# MMA8452QT_I2C.net
KiCad netlist of a schematic drawn in Altium Designer
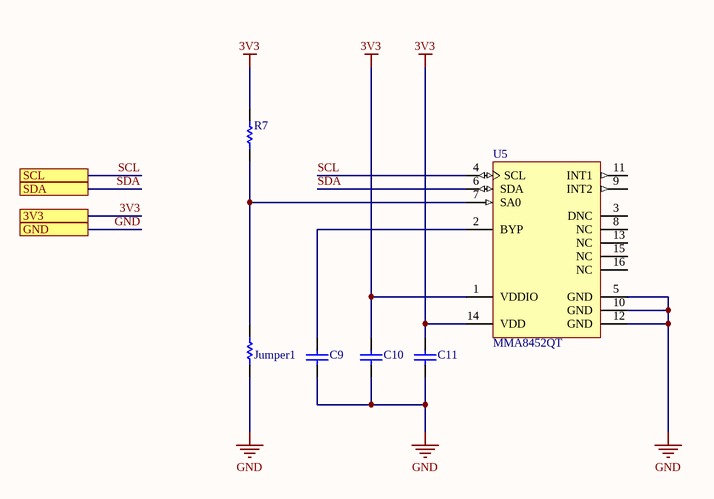
[diagram p0: MMA8452QT_I2C.SchDoc]

(export (version "E")
  (design (tool "Eeschema 10.0.6"))
  (components
    (comp (ref "C9")
      (value "C0805C104J5RAC7800")
      (footprint "CAPC2013X145X50NL20T25")
      (description "0.1µF ±5% 50V Ceramic Capacitor X7R 0805 (2012 Metric)")
      (fields (field (name "MANUFACTURER") "Kemet"))
      (libsource (lib "Altium Content Vault") (part "CAP"))
    )
    (comp (ref "C10")
      (value "C0805C104J5RAC7800")
      (footprint "CAPC2013X145X50NL20T25")
      (description "0.1µF ±5% 50V Ceramic Capacitor X7R 0805 (2012 Metric)")
      (fields (field (name "MANUFACTURER") "Kemet"))
      (libsource (lib "Altium Content Vault") (part "CAP"))
    )
    (comp (ref "C11")
      (value "08053D475KAT2A")
      (footprint "CAPC2013X140X50NL20T25")
      (description "4.7µF ±10% 25V Ceramic Capacitor X5R 0805 (2012 Metric)")
      (fields (field (name "MANUFACTURER") "AVX Interconnect / Elco"))
      (libsource (lib "Altium Content Vault") (part "CAP"))
    )
    (comp (ref "Jumper1")
      (value "~")
      (footprint "RESC2013X60X40NL20T25_A")
      (fields (field (name "TOLERANCE") "0.1%") (field (name "MANUFACTURER") "Panasonic"))
      (libsource (lib "Altium Content Vault") (part "RES-2"))
    )
    (comp (ref "R7")
      (value "RK73B2ATTD103J")
      (footprint "RESC2013X60X30NL20T20")
      (fields (field (name "MANUFACTURER") "KOA Speer"))
      (libsource (lib "Altium Content Vault") (part "RES"))
    )
    (comp (ref "U5")
      (value "MMA8452QT")
      (footprint "FRES-SOT1676-1_V")
      (fields (field (name "MANUFACTURER") "Freescale"))
      (libsource (lib "Altium Content Vault") (part "FRES-MMA8452Q-QFN-16"))
    )
  )
  (nets
    (net (code "1") (name "/SCL") (class "Default")
      (node (ref "U5") (pin "4") (pinfunction "SCL_4") (pintype "bidirectional"))
    )
    (net (code "2") (name "/SDA") (class "Default")
      (node (ref "U5") (pin "6") (pinfunction "SDA_6") (pintype "bidirectional"))
    )
    (net (code "3") (name "3V3") (class "Default")
      (node (ref "C10") (pin "2") (pinfunction "2_2") (pintype "passive"))
      (node (ref "C11") (pin "2") (pinfunction "2_2") (pintype "passive"))
      (node (ref "R7") (pin "2") (pinfunction "2_2") (pintype "passive"))
      (node (ref "U5") (pin "1") (pinfunction "VDDIO_1") (pintype "power_in"))
      (node (ref "U5") (pin "14") (pinfunction "VDD_14") (pintype "power_in"))
    )
    (net (code "4") (name "GND") (class "Default")
      (node (ref "C10") (pin "1") (pinfunction "1_1") (pintype "passive"))
      (node (ref "C11") (pin "1") (pinfunction "1_1") (pintype "passive"))
      (node (ref "C9") (pin "1") (pinfunction "1_1") (pintype "passive"))
      (node (ref "Jumper1") (pin "1") (pinfunction "1_1") (pintype "passive"))
      (node (ref "U5") (pin "10") (pinfunction "GND_10") (pintype "power_in"))
      (node (ref "U5") (pin "12") (pinfunction "GND_12") (pintype "power_in"))
      (node (ref "U5") (pin "5") (pinfunction "GND_5") (pintype "power_in"))
    )
    (net (code "5") (name "Net-(U5-BYP)") (class "Default")
      (node (ref "C9") (pin "2") (pinfunction "2_2") (pintype "passive"))
      (node (ref "U5") (pin "2") (pinfunction "BYP_2") (pintype "passive"))
    )
    (net (code "6") (name "Net-(U5-SA0)") (class "Default")
      (node (ref "Jumper1") (pin "2") (pinfunction "2_2") (pintype "passive"))
      (node (ref "R7") (pin "1") (pinfunction "1_1") (pintype "passive"))
      (node (ref "U5") (pin "7") (pinfunction "SA0_7") (pintype "input"))
    )
    (net (code "7") (name "unconnected-(U5-DNC-Pad3)") (class "Default")
      (node (ref "U5") (pin "3") (pinfunction "DNC_3") (pintype "passive"))
    )
    (net (code "8") (name "unconnected-(U5-INT1-Pad11)") (class "Default")
      (node (ref "U5") (pin "11") (pinfunction "INT1_11") (pintype "output"))
    )
    (net (code "9") (name "unconnected-(U5-INT2-Pad9)") (class "Default")
      (node (ref "U5") (pin "9") (pinfunction "INT2_9") (pintype "output"))
    )
    (net (code "10") (name "unconnected-(U5-NC-Pad8)") (class "Default")
      (node (ref "U5") (pin "8") (pinfunction "NC_8") (pintype "passive"))
    )
    (net (code "11") (name "unconnected-(U5-NC-Pad13)") (class "Default")
      (node (ref "U5") (pin "13") (pinfunction "NC_13") (pintype "passive"))
    )
    (net (code "12") (name "unconnected-(U5-NC-Pad15)") (class "Default")
      (node (ref "U5") (pin "15") (pinfunction "NC_15") (pintype "passive"))
    )
    (net (code "13") (name "unconnected-(U5-NC-Pad16)") (class "Default")
      (node (ref "U5") (pin "16") (pinfunction "NC_16") (pintype "passive"))
    )
  )
)
